# SCH_UM982-and-F9P-adapter_2025-07-17.net
KiCad netlist of a schematic drawn in EasyEDA
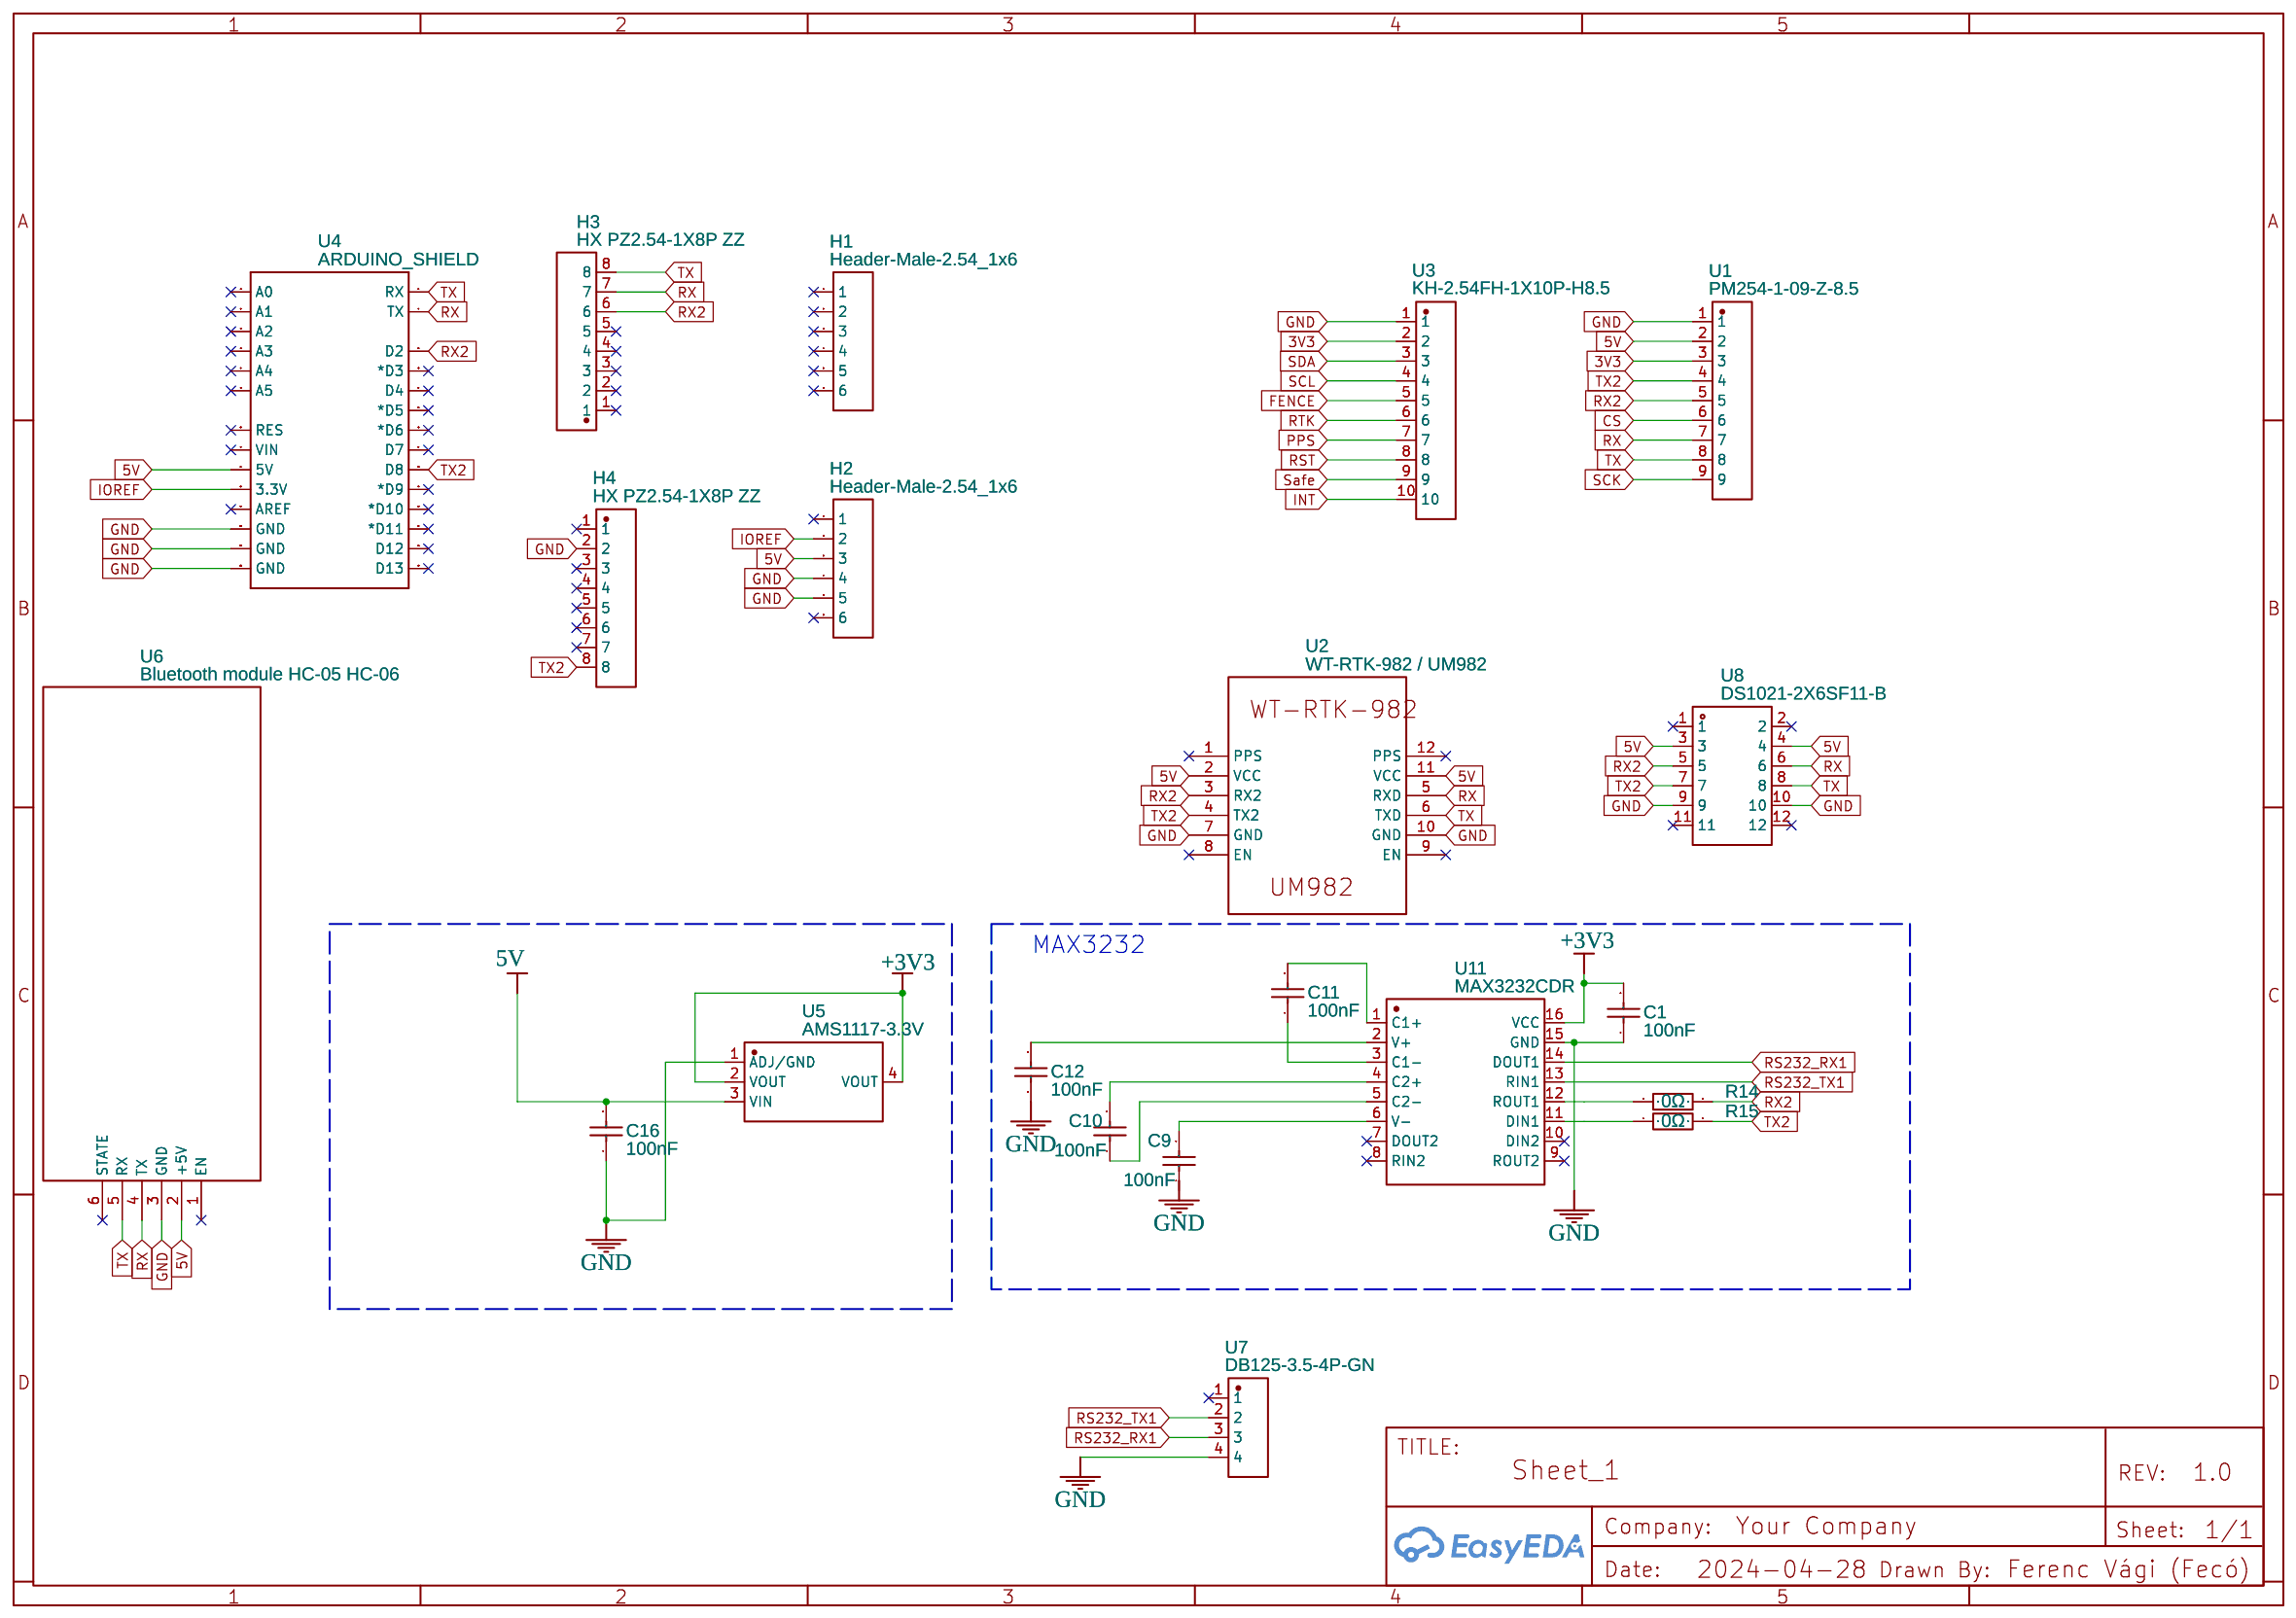
[diagram p0: schematic sheet]

(export (version "E")
  (design (tool "Eeschema 10.0.6"))
  (components
    (comp (ref "C1")
      (value "100nF")
      (fields
        (field (name "Manufacturer Part") "CL31B104KBCNNNC")
        (field (name "Manufacturer") "SAMSUNG(三星)")
      )
      (libsource (lib "") (part "CL31B104KBCNNNC"))
    )
    (comp (ref "C9")
      (value "100nF")
      (fields
        (field (name "Manufacturer Part") "CL31B104KBCNNNC")
        (field (name "Manufacturer") "SAMSUNG(三星)")
      )
      (libsource (lib "") (part "CL31B104KBCNNNC"))
    )
    (comp (ref "C10")
      (value "100nF")
      (fields
        (field (name "Manufacturer Part") "CL31B104KBCNNNC")
        (field (name "Manufacturer") "SAMSUNG(三星)")
      )
      (libsource (lib "") (part "CL31B104KBCNNNC"))
    )
    (comp (ref "C11")
      (value "100nF")
      (fields
        (field (name "Manufacturer Part") "CL31B104KBCNNNC")
        (field (name "Manufacturer") "SAMSUNG(三星)")
      )
      (libsource (lib "") (part "CL31B104KBCNNNC"))
    )
    (comp (ref "C12")
      (value "100nF")
      (fields
        (field (name "Manufacturer Part") "CL31B104KBCNNNC")
        (field (name "Manufacturer") "SAMSUNG(三星)")
      )
      (libsource (lib "") (part "CL31B104KBCNNNC"))
    )
    (comp (ref "C16")
      (value "100nF")
      (fields
        (field (name "Manufacturer Part") "CL31B104KBCNNNC")
        (field (name "Manufacturer") "SAMSUNG(三星)")
      )
      (libsource (lib "") (part "CL31B104KBCNNNC"))
    )
    (comp (ref "H1")
      (value "Header-Male-2.54_1x6")
      (fields (field (name "Manufacturer Part") "2.54-1x6P直针") (field (name "Manufacturer") "BOOMELE(博穆精密)"))
      (libsource (lib "") (part "Header-Male-2.54_1x6"))
    )
    (comp (ref "H2")
      (value "Header-Male-2.54_1x6")
      (fields (field (name "Manufacturer Part") "2.54-1x6P直针") (field (name "Manufacturer") "BOOMELE(博穆精密)"))
      (libsource (lib "") (part "Header-Male-2.54_1x6"))
    )
    (comp (ref "H3")
      (value "HX PZ2.54-1X8P ZZ")
      (fields
        (field (name "Manufacturer Part") "HX PZ2.54-1x8P ZZ")
        (field (name "Manufacturer") "hanxia(韩下)")
      )
      (libsource (lib "") (part "HX PZ2.54-1X8P ZZ"))
    )
    (comp (ref "H4")
      (value "HX PZ2.54-1X8P ZZ")
      (fields
        (field (name "Manufacturer Part") "HX PZ2.54-1x8P ZZ")
        (field (name "Manufacturer") "hanxia(韩下)")
      )
      (libsource (lib "") (part "HX PZ2.54-1X8P ZZ_1"))
    )
    (comp (ref "R14")
      (value "0Ω")
      (fields
        (field (name "Manufacturer Part") "0805W8F0000T5E")
        (field (name "Manufacturer") "UNI-ROYAL(厚声)")
      )
      (libsource (lib "") (part "0805W8F0000T5E"))
    )
    (comp (ref "R15")
      (value "0Ω")
      (fields
        (field (name "Manufacturer Part") "0805W8F0000T5E")
        (field (name "Manufacturer") "UNI-ROYAL(厚声)")
      )
      (libsource (lib "") (part "0805W8F0000T5E"))
    )
    (comp (ref "U1")
      (value "PM254-1-09-Z-8.5")
      (fields (field (name "Manufacturer") "HCTL(华灿天禄)"))
      (libsource (lib "") (part "PM254-1-09-Z-8.5"))
    )
    (comp (ref "U2")
      (value "WT-RTK-982 / UM982")
      (fields (field (name "Manufacturer Part") "WT-RTK-982") (field (name "Manufacturer") "WitMotion"))
      (libsource (lib "") (part "WT-RTK-982 / UM982"))
    )
    (comp (ref "U3")
      (value "KH-2.54FH-1X10P-H8.5")
      (fields (field (name "Manufacturer") "kinghelm(金航标)"))
      (libsource (lib "") (part "KH-2.54FH-1X10P-H8.5"))
    )
    (comp (ref "U4") (value "ARDUINO_SHIELD") (libsource (lib "") (part "ARDUINO_SHIELD")))
    (comp (ref "U5")
      (value "AMS1117-3.3V")
      (fields (field (name "Manufacturer") "WPMtek(维攀)"))
      (libsource (lib "") (part "AMS1117-3.3V"))
    )
    (comp (ref "U6")
      (value "Bluetooth module HC-05 HC-06")
      (fields (field (name "Manufacturer Part") "HC05"))
      (libsource (lib "") (part "Bluetooth module HC-05 HC-06"))
    )
    (comp (ref "U7")
      (value "DB125-3.5-4P-GN")
      (fields
        (field (name "Manufacturer Part") "DB125-3.5-4P-GN-S")
        (field (name "Manufacturer") "DORABO(地博电气)")
      )
      (libsource (lib "") (part "DB125-3.5-4P-GN"))
    )
    (comp (ref "U8")
      (value "DS1021-2X6SF11-B")
      (fields (field (name "Manufacturer Part") "DS1021-2x6SF11-B") (field (name "Manufacturer") "CONNFLY"))
      (libsource (lib "") (part "DS1021-2X6SF11-B"))
    )
    (comp (ref "U11")
      (value "MAX3232CDR")
      (fields (field (name "Manufacturer") "TI(德州仪器)"))
      (libsource (lib "") (part "MAX3232CDR"))
    )
  )
  (nets
    (net (code "1") (name "+3V3") (class "Default")
      (node (ref "C1") (pin "2") (pinfunction "2_2") (pintype "input"))
      (node (ref "U11") (pin "16") (pinfunction "VCC_16") (pintype "unspecified"))
      (node (ref "U5") (pin "2") (pinfunction "VOUT_2") (pintype "unspecified"))
      (node (ref "U5") (pin "4") (pinfunction "VOUT_4") (pintype "unspecified"))
    )
    (net (code "2") (name "3V3") (class "Default")
      (node (ref "U1") (pin "3") (pinfunction "3_3") (pintype "unspecified"))
      (node (ref "U3") (pin "2") (pinfunction "2_2") (pintype "unspecified"))
    )
    (net (code "3") (name "5V") (class "Default")
      (node (ref "C16") (pin "2") (pinfunction "2_2") (pintype "input"))
      (node (ref "H2") (pin "3") (pinfunction "3_3") (pintype "input"))
      (node (ref "U1") (pin "2") (pinfunction "2_2") (pintype "unspecified"))
      (node (ref "U2") (pin "11") (pinfunction "VCC_11") (pintype "unspecified"))
      (node (ref "U2") (pin "2") (pinfunction "VCC_2") (pintype "unspecified"))
      (node (ref "U4") (pin "5V") (pinfunction "5V_5V") (pintype "unspecified"))
      (node (ref "U5") (pin "3") (pinfunction "VIN_3") (pintype "unspecified"))
      (node (ref "U6") (pin "2") (pinfunction "+5V_2") (pintype "unspecified"))
      (node (ref "U8") (pin "3") (pinfunction "3_3") (pintype "unspecified"))
      (node (ref "U8") (pin "4") (pinfunction "4_4") (pintype "unspecified"))
    )
    (net (code "4") (name "CS") (class "Default")
      (node (ref "U1") (pin "6") (pinfunction "6_6") (pintype "unspecified"))
    )
    (net (code "5") (name "FENCE") (class "Default")
      (node (ref "U3") (pin "5") (pinfunction "5_5") (pintype "unspecified"))
    )
    (net (code "6") (name "GND") (class "Default")
      (node (ref "C1") (pin "1") (pinfunction "1_1") (pintype "input"))
      (node (ref "C12") (pin "1") (pinfunction "1_1") (pintype "input"))
      (node (ref "C16") (pin "1") (pinfunction "1_1") (pintype "input"))
      (node (ref "C9") (pin "1") (pinfunction "1_1") (pintype "input"))
      (node (ref "H2") (pin "4") (pinfunction "4_4") (pintype "input"))
      (node (ref "H2") (pin "5") (pinfunction "5_5") (pintype "input"))
      (node (ref "H4") (pin "2") (pinfunction "2_2") (pintype "unspecified"))
      (node (ref "U1") (pin "1") (pinfunction "1_1") (pintype "unspecified"))
      (node (ref "U11") (pin "15") (pinfunction "GND_15") (pintype "unspecified"))
      (node (ref "U2") (pin "10") (pinfunction "GND_10") (pintype "unspecified"))
      (node (ref "U2") (pin "7") (pinfunction "GND_7") (pintype "unspecified"))
      (node (ref "U3") (pin "1") (pinfunction "1_1") (pintype "unspecified"))
      (node (ref "U4") (pin "GND@0") (pinfunction "GND_GND@0") (pintype "unspecified"))
      (node (ref "U4") (pin "GND@1") (pinfunction "GND_GND@1") (pintype "unspecified"))
      (node (ref "U4") (pin "GND@2") (pinfunction "GND_GND@2") (pintype "unspecified"))
      (node (ref "U5") (pin "1") (pinfunction "ADJ/GND_1") (pintype "unspecified"))
      (node (ref "U6") (pin "3") (pinfunction "GND_3") (pintype "unspecified"))
      (node (ref "U7") (pin "4") (pinfunction "4_4") (pintype "unspecified"))
      (node (ref "U8") (pin "10") (pinfunction "10_10") (pintype "unspecified"))
      (node (ref "U8") (pin "9") (pinfunction "9_9") (pintype "unspecified"))
    )
    (net (code "7") (name "INT") (class "Default")
      (node (ref "U3") (pin "10") (pinfunction "10_10") (pintype "unspecified"))
    )
    (net (code "8") (name "IOREF") (class "Default")
      (node (ref "H2") (pin "2") (pinfunction "2_2") (pintype "input"))
      (node (ref "U4") (pin "3.3V") (pinfunction "3.3V_3.3V") (pintype "unspecified"))
    )
    (net (code "9") (name "Net-(U11-C1+)") (class "Default")
      (node (ref "C11") (pin "2") (pinfunction "2_2") (pintype "input"))
      (node (ref "U11") (pin "1") (pinfunction "C1+_1") (pintype "unspecified"))
    )
    (net (code "10") (name "Net-(U11-C1-)") (class "Default")
      (node (ref "C11") (pin "1") (pinfunction "1_1") (pintype "input"))
      (node (ref "U11") (pin "3") (pinfunction "C1-_3") (pintype "unspecified"))
    )
    (net (code "11") (name "Net-(U11-C2+)") (class "Default")
      (node (ref "C10") (pin "2") (pinfunction "2_2") (pintype "input"))
      (node (ref "U11") (pin "4") (pinfunction "C2+_4") (pintype "unspecified"))
    )
    (net (code "12") (name "Net-(U11-C2-)") (class "Default")
      (node (ref "C10") (pin "1") (pinfunction "1_1") (pintype "input"))
      (node (ref "U11") (pin "5") (pinfunction "C2-_5") (pintype "unspecified"))
    )
    (net (code "13") (name "Net-(U11-DIN1)") (class "Default")
      (node (ref "R15") (pin "1") (pinfunction "1_1") (pintype "input"))
      (node (ref "U11") (pin "11") (pinfunction "DIN1_11") (pintype "unspecified"))
    )
    (net (code "14") (name "Net-(U11-ROUT1)") (class "Default")
      (node (ref "R14") (pin "1") (pinfunction "1_1") (pintype "input"))
      (node (ref "U11") (pin "12") (pinfunction "ROUT1_12") (pintype "unspecified"))
    )
    (net (code "15") (name "Net-(U11-V+)") (class "Default")
      (node (ref "C12") (pin "2") (pinfunction "2_2") (pintype "input"))
      (node (ref "U11") (pin "2") (pinfunction "V+_2") (pintype "unspecified"))
    )
    (net (code "16") (name "Net-(U11-V-)") (class "Default")
      (node (ref "C9") (pin "2") (pinfunction "2_2") (pintype "input"))
      (node (ref "U11") (pin "6") (pinfunction "V-_6") (pintype "unspecified"))
    )
    (net (code "17") (name "PPS") (class "Default")
      (node (ref "U3") (pin "7") (pinfunction "7_7") (pintype "unspecified"))
    )
    (net (code "18") (name "RS232_RX1") (class "Default")
      (node (ref "U11") (pin "14") (pinfunction "DOUT1_14") (pintype "unspecified"))
      (node (ref "U7") (pin "3") (pinfunction "3_3") (pintype "unspecified"))
    )
    (net (code "19") (name "RS232_TX1") (class "Default")
      (node (ref "U11") (pin "13") (pinfunction "RIN1_13") (pintype "unspecified"))
      (node (ref "U7") (pin "2") (pinfunction "2_2") (pintype "unspecified"))
    )
    (net (code "20") (name "RST") (class "Default")
      (node (ref "U3") (pin "8") (pinfunction "8_8") (pintype "unspecified"))
    )
    (net (code "21") (name "RTK") (class "Default")
      (node (ref "U3") (pin "6") (pinfunction "6_6") (pintype "unspecified"))
    )
    (net (code "22") (name "RX") (class "Default")
      (node (ref "H3") (pin "7") (pinfunction "7_7") (pintype "unspecified"))
      (node (ref "U1") (pin "7") (pinfunction "7_7") (pintype "unspecified"))
      (node (ref "U2") (pin "5") (pinfunction "RXD_5") (pintype "unspecified"))
      (node (ref "U4") (pin "TX") (pinfunction "TX_TX") (pintype "unspecified"))
      (node (ref "U6") (pin "4") (pinfunction "TX_4") (pintype "unspecified"))
      (node (ref "U8") (pin "6") (pinfunction "6_6") (pintype "unspecified"))
    )
    (net (code "23") (name "RX2") (class "Default")
      (node (ref "H3") (pin "6") (pinfunction "6_6") (pintype "unspecified"))
      (node (ref "R14") (pin "2") (pinfunction "2_2") (pintype "input"))
      (node (ref "U1") (pin "5") (pinfunction "5_5") (pintype "unspecified"))
      (node (ref "U2") (pin "3") (pinfunction "RX2_3") (pintype "unspecified"))
      (node (ref "U4") (pin "D2") (pinfunction "D2_D2") (pintype "unspecified"))
      (node (ref "U8") (pin "5") (pinfunction "5_5") (pintype "unspecified"))
    )
    (net (code "24") (name "SCK") (class "Default")
      (node (ref "U1") (pin "9") (pinfunction "9_9") (pintype "unspecified"))
    )
    (net (code "25") (name "SCL") (class "Default")
      (node (ref "U3") (pin "4") (pinfunction "4_4") (pintype "unspecified"))
    )
    (net (code "26") (name "SDA") (class "Default")
      (node (ref "U3") (pin "3") (pinfunction "3_3") (pintype "unspecified"))
    )
    (net (code "27") (name "Safe") (class "Default")
      (node (ref "U3") (pin "9") (pinfunction "9_9") (pintype "unspecified"))
    )
    (net (code "28") (name "TX") (class "Default")
      (node (ref "H3") (pin "8") (pinfunction "8_8") (pintype "unspecified"))
      (node (ref "U1") (pin "8") (pinfunction "8_8") (pintype "unspecified"))
      (node (ref "U2") (pin "6") (pinfunction "TXD_6") (pintype "unspecified"))
      (node (ref "U4") (pin "RX") (pinfunction "RX_RX") (pintype "unspecified"))
      (node (ref "U6") (pin "5") (pinfunction "RX_5") (pintype "unspecified"))
      (node (ref "U8") (pin "8") (pinfunction "8_8") (pintype "unspecified"))
    )
    (net (code "29") (name "TX2") (class "Default")
      (node (ref "H4") (pin "8") (pinfunction "8_8") (pintype "unspecified"))
      (node (ref "R15") (pin "2") (pinfunction "2_2") (pintype "input"))
      (node (ref "U1") (pin "4") (pinfunction "4_4") (pintype "unspecified"))
      (node (ref "U2") (pin "4") (pinfunction "TX2_4") (pintype "unspecified"))
      (node (ref "U4") (pin "D8") (pinfunction "D8_D8") (pintype "unspecified"))
      (node (ref "U8") (pin "7") (pinfunction "7_7") (pintype "unspecified"))
    )
    (net (code "30") (name "unconnected-(H1-Pad1)") (class "Default")
      (node (ref "H1") (pin "1") (pinfunction "1_1") (pintype "input+no_connect"))
    )
    (net (code "31") (name "unconnected-(H1-Pad2)") (class "Default")
      (node (ref "H1") (pin "2") (pinfunction "2_2") (pintype "input+no_connect"))
    )
    (net (code "32") (name "unconnected-(H1-Pad3)") (class "Default")
      (node (ref "H1") (pin "3") (pinfunction "3_3") (pintype "input+no_connect"))
    )
    (net (code "33") (name "unconnected-(H1-Pad4)") (class "Default")
      (node (ref "H1") (pin "4") (pinfunction "4_4") (pintype "input+no_connect"))
    )
    (net (code "34") (name "unconnected-(H1-Pad5)") (class "Default")
      (node (ref "H1") (pin "5") (pinfunction "5_5") (pintype "input+no_connect"))
    )
    (net (code "35") (name "unconnected-(H1-Pad6)") (class "Default")
      (node (ref "H1") (pin "6") (pinfunction "6_6") (pintype "input+no_connect"))
    )
    (net (code "36") (name "unconnected-(H2-Pad1)") (class "Default")
      (node (ref "H2") (pin "1") (pinfunction "1_1") (pintype "input+no_connect"))
    )
    (net (code "37") (name "unconnected-(H2-Pad6)") (class "Default")
      (node (ref "H2") (pin "6") (pinfunction "6_6") (pintype "input+no_connect"))
    )
    (net (code "38") (name "unconnected-(H3-Pad1)") (class "Default")
      (node (ref "H3") (pin "1") (pinfunction "1_1") (pintype "unspecified+no_connect"))
    )
    (net (code "39") (name "unconnected-(H3-Pad2)") (class "Default")
      (node (ref "H3") (pin "2") (pinfunction "2_2") (pintype "unspecified+no_connect"))
    )
    (net (code "40") (name "unconnected-(H3-Pad3)") (class "Default")
      (node (ref "H3") (pin "3") (pinfunction "3_3") (pintype "unspecified+no_connect"))
    )
    (net (code "41") (name "unconnected-(H3-Pad4)") (class "Default")
      (node (ref "H3") (pin "4") (pinfunction "4_4") (pintype "unspecified+no_connect"))
    )
    (net (code "42") (name "unconnected-(H3-Pad5)") (class "Default")
      (node (ref "H3") (pin "5") (pinfunction "5_5") (pintype "unspecified+no_connect"))
    )
    (net (code "43") (name "unconnected-(H4-Pad1)") (class "Default")
      (node (ref "H4") (pin "1") (pinfunction "1_1") (pintype "unspecified+no_connect"))
    )
    (net (code "44") (name "unconnected-(H4-Pad3)") (class "Default")
      (node (ref "H4") (pin "3") (pinfunction "3_3") (pintype "unspecified+no_connect"))
    )
    (net (code "45") (name "unconnected-(H4-Pad4)") (class "Default")
      (node (ref "H4") (pin "4") (pinfunction "4_4") (pintype "unspecified+no_connect"))
    )
    (net (code "46") (name "unconnected-(H4-Pad5)") (class "Default")
      (node (ref "H4") (pin "5") (pinfunction "5_5") (pintype "unspecified+no_connect"))
    )
    (net (code "47") (name "unconnected-(H4-Pad6)") (class "Default")
      (node (ref "H4") (pin "6") (pinfunction "6_6") (pintype "unspecified+no_connect"))
    )
    (net (code "48") (name "unconnected-(H4-Pad7)") (class "Default")
      (node (ref "H4") (pin "7") (pinfunction "7_7") (pintype "unspecified+no_connect"))
    )
    (net (code "49") (name "unconnected-(U2-EN-Pad8)") (class "Default")
      (node (ref "U2") (pin "8") (pinfunction "EN_8") (pintype "unspecified+no_connect"))
    )
    (net (code "50") (name "unconnected-(U2-EN-Pad9)") (class "Default")
      (node (ref "U2") (pin "9") (pinfunction "EN_9") (pintype "unspecified+no_connect"))
    )
    (net (code "51") (name "unconnected-(U2-PPS-Pad1)") (class "Default")
      (node (ref "U2") (pin "1") (pinfunction "PPS_1") (pintype "unspecified+no_connect"))
    )
    (net (code "52") (name "unconnected-(U2-PPS-Pad12)") (class "Default")
      (node (ref "U2") (pin "12") (pinfunction "PPS_12") (pintype "unspecified+no_connect"))
    )
    (net (code "53") (name "unconnected-(U4-*D3-PadD3)") (class "Default")
      (node (ref "U4") (pin "D3") (pinfunction "*D3_D3") (pintype "unspecified+no_connect"))
    )
    (net (code "54") (name "unconnected-(U4-*D5-PadD5)") (class "Default")
      (node (ref "U4") (pin "D5") (pinfunction "*D5_D5") (pintype "unspecified+no_connect"))
    )
    (net (code "55") (name "unconnected-(U4-*D6-PadD6)") (class "Default")
      (node (ref "U4") (pin "D6") (pinfunction "*D6_D6") (pintype "unspecified+no_connect"))
    )
    (net (code "56") (name "unconnected-(U4-*D9-PadD9)") (class "Default")
      (node (ref "U4") (pin "D9") (pinfunction "*D9_D9") (pintype "unspecified+no_connect"))
    )
    (net (code "57") (name "unconnected-(U4-*D10-PadD10)") (class "Default")
      (node (ref "U4") (pin "D10") (pinfunction "*D10_D10") (pintype "unspecified+no_connect"))
    )
    (net (code "58") (name "unconnected-(U4-*D11-PadD11)") (class "Default")
      (node (ref "U4") (pin "D11") (pinfunction "*D11_D11") (pintype "unspecified+no_connect"))
    )
    (net (code "59") (name "unconnected-(U4-PadA0)") (class "Default")
      (node (ref "U4") (pin "A0") (pinfunction "A0_A0") (pintype "unspecified+no_connect"))
    )
    (net (code "60") (name "unconnected-(U4-PadA1)") (class "Default")
      (node (ref "U4") (pin "A1") (pinfunction "A1_A1") (pintype "unspecified+no_connect"))
    )
    (net (code "61") (name "unconnected-(U4-PadA2)") (class "Default")
      (node (ref "U4") (pin "A2") (pinfunction "A2_A2") (pintype "unspecified+no_connect"))
    )
    (net (code "62") (name "unconnected-(U4-PadA3)") (class "Default")
      (node (ref "U4") (pin "A3") (pinfunction "A3_A3") (pintype "unspecified+no_connect"))
    )
    (net (code "63") (name "unconnected-(U4-PadA4)") (class "Default")
      (node (ref "U4") (pin "A4") (pinfunction "A4_A4") (pintype "unspecified+no_connect"))
    )
    (net (code "64") (name "unconnected-(U4-PadA5)") (class "Default")
      (node (ref "U4") (pin "A5") (pinfunction "A5_A5") (pintype "unspecified+no_connect"))
    )
    (net (code "65") (name "unconnected-(U4-PadAREF)") (class "Default")
      (node (ref "U4") (pin "AREF") (pinfunction "AREF_AREF") (pintype "unspecified+no_connect"))
    )
    (net (code "66") (name "unconnected-(U4-PadD4)") (class "Default")
      (node (ref "U4") (pin "D4") (pinfunction "D4_D4") (pintype "unspecified+no_connect"))
    )
    (net (code "67") (name "unconnected-(U4-PadD7)") (class "Default")
      (node (ref "U4") (pin "D7") (pinfunction "D7_D7") (pintype "unspecified+no_connect"))
    )
    (net (code "68") (name "unconnected-(U4-PadD12)") (class "Default")
      (node (ref "U4") (pin "D12") (pinfunction "D12_D12") (pintype "unspecified+no_connect"))
    )
    (net (code "69") (name "unconnected-(U4-PadD13)") (class "Default")
      (node (ref "U4") (pin "D13") (pinfunction "D13_D13") (pintype "unspecified+no_connect"))
    )
    (net (code "70") (name "unconnected-(U4-PadRES)") (class "Default")
      (node (ref "U4") (pin "RES") (pinfunction "RES_RES") (pintype "unspecified+no_connect"))
    )
    (net (code "71") (name "unconnected-(U4-PadVIN)") (class "Default")
      (node (ref "U4") (pin "VIN") (pinfunction "VIN_VIN") (pintype "unspecified+no_connect"))
    )
    (net (code "72") (name "unconnected-(U6-EN-Pad1)") (class "Default")
      (node (ref "U6") (pin "1") (pinfunction "EN_1") (pintype "unspecified+no_connect"))
    )
    (net (code "73") (name "unconnected-(U6-STATE-Pad6)") (class "Default")
      (node (ref "U6") (pin "6") (pinfunction "STATE_6") (pintype "unspecified+no_connect"))
    )
    (net (code "74") (name "unconnected-(U7-Pad1)") (class "Default")
      (node (ref "U7") (pin "1") (pinfunction "1_1") (pintype "unspecified+no_connect"))
    )
    (net (code "75") (name "unconnected-(U8-Pad1)") (class "Default")
      (node (ref "U8") (pin "1") (pinfunction "1_1") (pintype "unspecified+no_connect"))
    )
    (net (code "76") (name "unconnected-(U8-Pad2)") (class "Default")
      (node (ref "U8") (pin "2") (pinfunction "2_2") (pintype "unspecified+no_connect"))
    )
    (net (code "77") (name "unconnected-(U8-Pad11)") (class "Default")
      (node (ref "U8") (pin "11") (pinfunction "11_11") (pintype "unspecified+no_connect"))
    )
    (net (code "78") (name "unconnected-(U8-Pad12)") (class "Default")
      (node (ref "U8") (pin "12") (pinfunction "12_12") (pintype "unspecified+no_connect"))
    )
    (net (code "79") (name "unconnected-(U11-DIN2-Pad10)") (class "Default")
      (node (ref "U11") (pin "10") (pinfunction "DIN2_10") (pintype "unspecified+no_connect"))
    )
    (net (code "80") (name "unconnected-(U11-DOUT2-Pad7)") (class "Default")
      (node (ref "U11") (pin "7") (pinfunction "DOUT2_7") (pintype "unspecified+no_connect"))
    )
    (net (code "81") (name "unconnected-(U11-RIN2-Pad8)") (class "Default")
      (node (ref "U11") (pin "8") (pinfunction "RIN2_8") (pintype "unspecified+no_connect"))
    )
    (net (code "82") (name "unconnected-(U11-ROUT2-Pad9)") (class "Default")
      (node (ref "U11") (pin "9") (pinfunction "ROUT2_9") (pintype "unspecified+no_connect"))
    )
  )
)
